# FIO_M.net
KiCad netlist of a schematic drawn in EAGLE
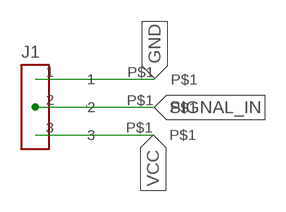
[diagram p0: schematic, sheet 1]

(export (version "E")
  (design (tool "Eeschema 10.0.6"))
  (components
    (comp (ref "J1")
      (value "CONECTOR_MACHO")
      (footprint "eagle-import:3CONECTOR")
      (libsource (lib "eagle-import") (part "CONECTOR_MACHO"))
    )
    (comp (ref "U$1")
      (value "PAD")
      (footprint "eagle-import:PAD")
      (libsource (lib "eagle-import") (part "PAD"))
    )
    (comp (ref "U$2")
      (value "PAD")
      (footprint "eagle-import:PAD")
      (libsource (lib "eagle-import") (part "PAD"))
    )
    (comp (ref "VCC")
      (value "PAD")
      (footprint "eagle-import:PAD")
      (libsource (lib "eagle-import") (part "PAD"))
    )
  )
  (nets
    (net (code "1") (name "GND") (class "Default")
      (node (ref "J1") (pin "1") (pinfunction "1_1") (pintype "bidirectional"))
      (node (ref "U$1") (pin "P$1") (pinfunction "P$1_P$1") (pintype "bidirectional"))
    )
    (net (code "2") (name "SIGNAL_IN") (class "Default")
      (node (ref "J1") (pin "2") (pinfunction "2_2") (pintype "bidirectional"))
      (node (ref "U$2") (pin "P$1") (pinfunction "P$1_P$1") (pintype "bidirectional"))
    )
    (net (code "3") (name "VCC") (class "Default")
      (node (ref "J1") (pin "3") (pinfunction "3_3") (pintype "bidirectional"))
      (node (ref "VCC") (pin "P$1") (pinfunction "P$1_P$1") (pintype "bidirectional"))
    )
  )
)
